# antenna_analyzer_rev7.net
KiCad netlist of a schematic drawn in EAGLE
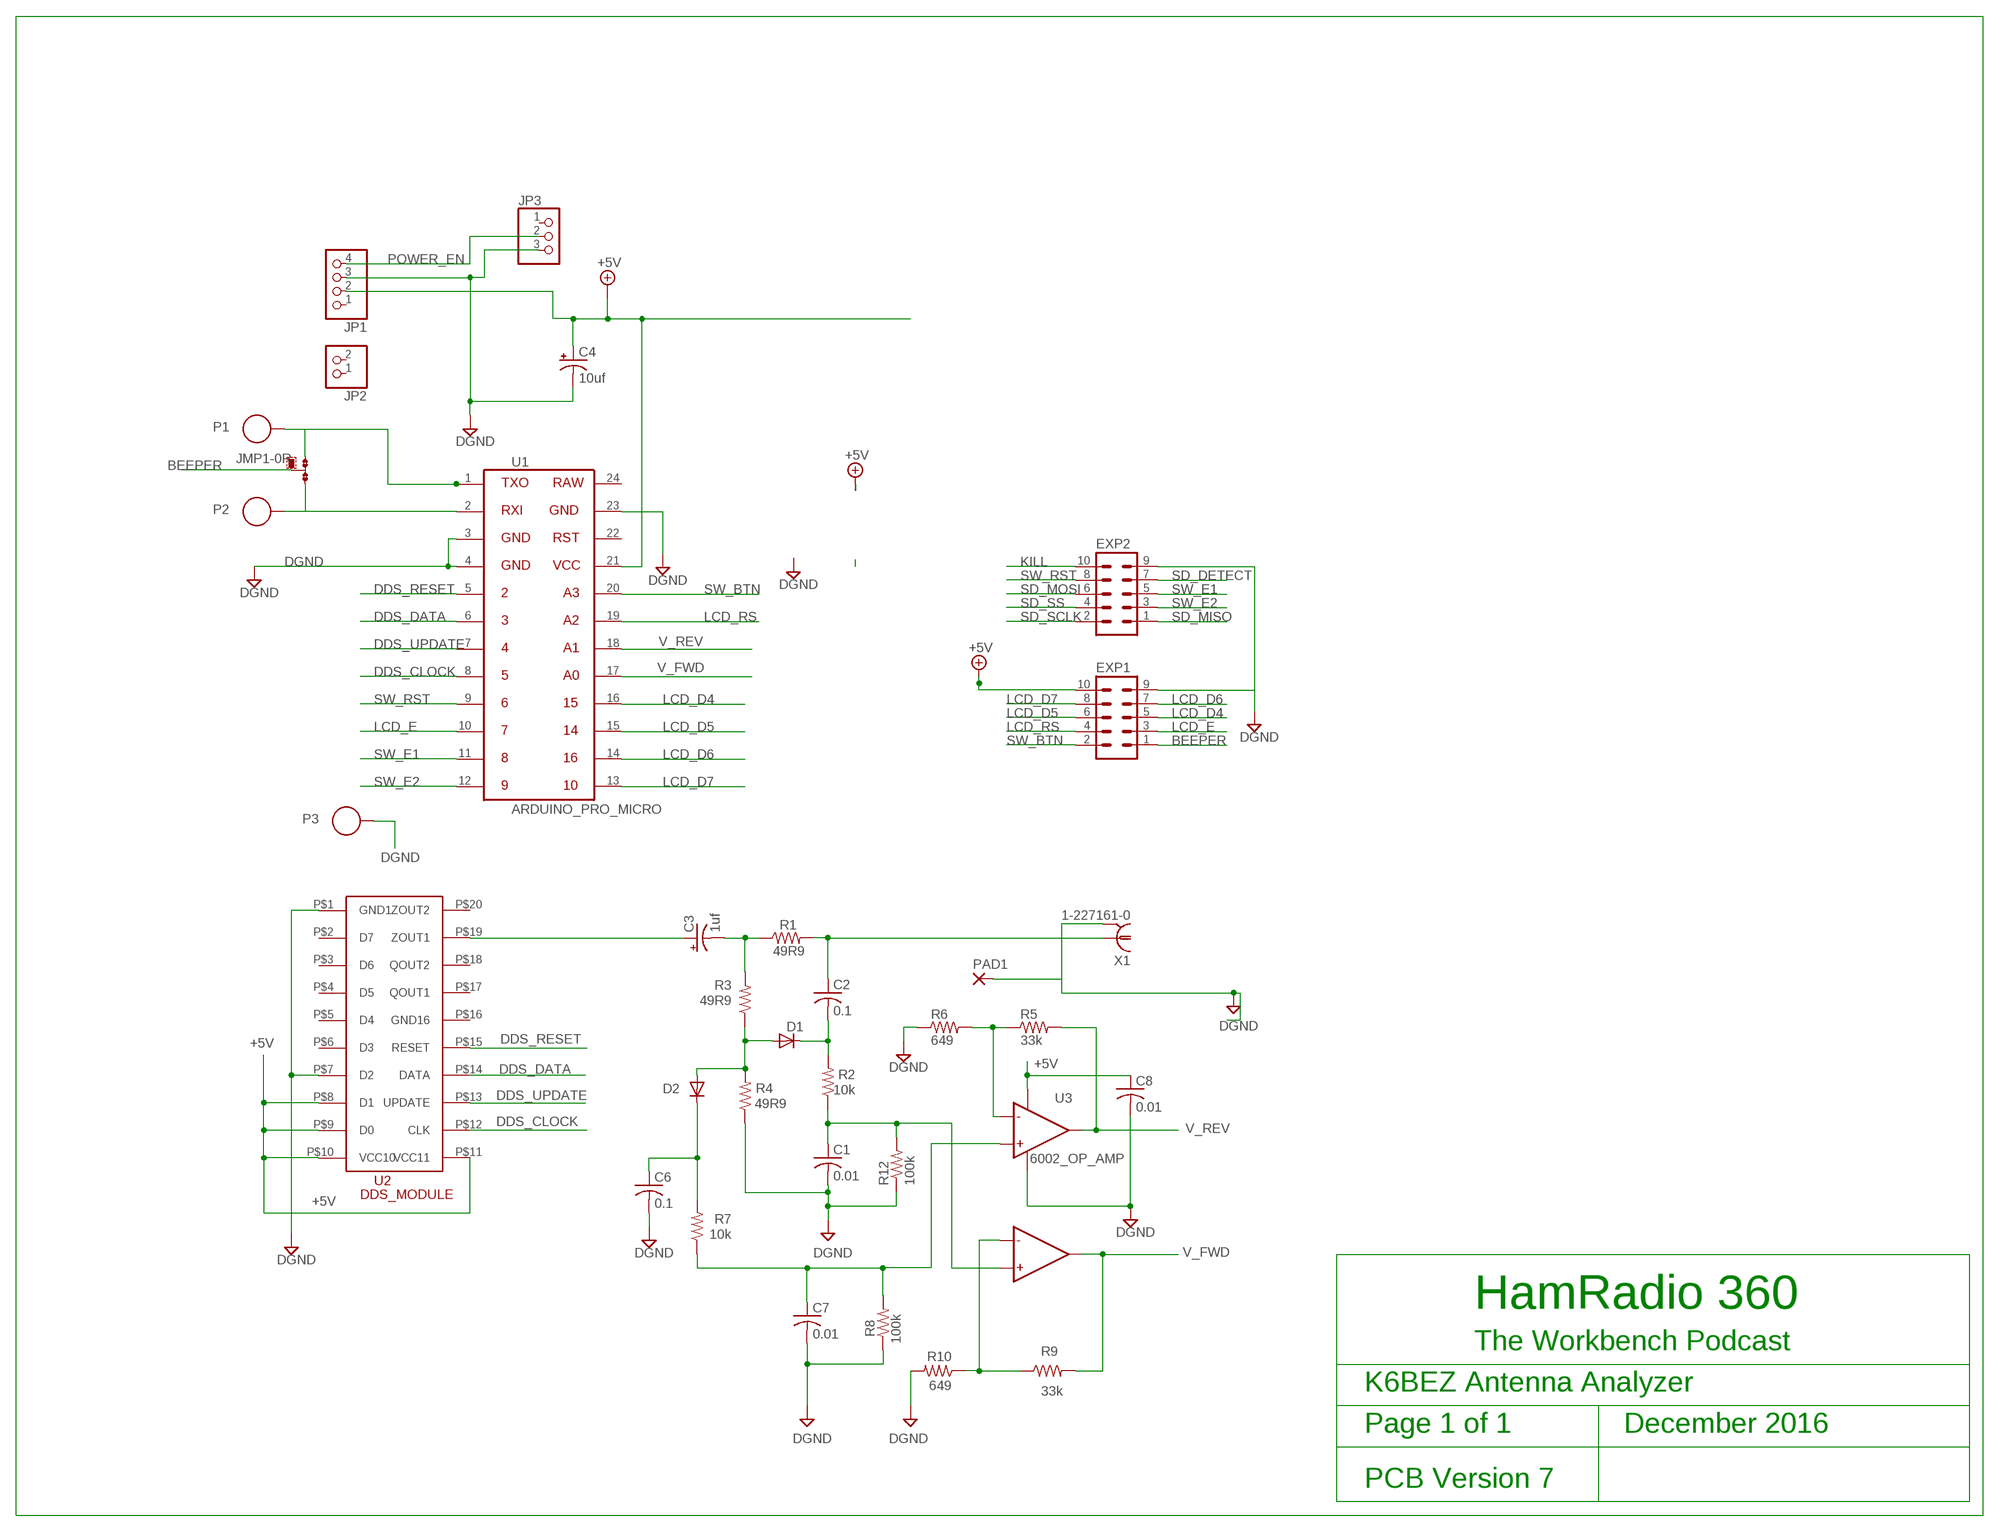
[diagram p0: schematic, sheet 1]

(export (version "E")
  (design (tool "Eeschema 10.0.6"))
  (components
    (comp (ref "C1")
      (value "0.01")
      (footprint "eagle-import:C025-025X050")
      (libsource (lib "eagle-import") (part "C-US025-025X050"))
    )
    (comp (ref "C2")
      (value "0.1")
      (footprint "eagle-import:C025-025X050")
      (libsource (lib "eagle-import") (part "C-US025-025X050"))
    )
    (comp (ref "C3")
      (value "1uf")
      (footprint "eagle-import:E1,8-4")
      (libsource (lib "eagle-import") (part "CPOL-USE1.8-4"))
    )
    (comp (ref "C4")
      (value "10uf")
      (footprint "eagle-import:E1,8-4")
      (libsource (lib "eagle-import") (part "CPOL-USE1.8-4"))
    )
    (comp (ref "C6")
      (value "0.1")
      (footprint "eagle-import:C025-025X050")
      (libsource (lib "eagle-import") (part "C-US025-025X050"))
    )
    (comp (ref "C7")
      (value "0.01")
      (footprint "eagle-import:C025-025X050")
      (libsource (lib "eagle-import") (part "C-US025-025X050"))
    )
    (comp (ref "C8")
      (value "0.01")
      (footprint "eagle-import:C025-025X050")
      (libsource (lib "eagle-import") (part "C-US025-025X050"))
    )
    (comp (ref "D1")
      (value "AA143")
      (footprint "eagle-import:DO35-7")
      (libsource (lib "eagle-import") (part "1N4148DO35-7"))
    )
    (comp (ref "D2")
      (value "AA143")
      (footprint "eagle-import:DO35-7")
      (libsource (lib "eagle-import") (part "1N4148DO35-7"))
    )
    (comp (ref "EXP1")
      (value "MA05-2")
      (footprint "eagle-import:MA05-2")
      (libsource (lib "eagle-import") (part "MA05-2"))
    )
    (comp (ref "EXP2")
      (value "MA05-2")
      (footprint "eagle-import:MA05-2")
      (libsource (lib "eagle-import") (part "MA05-2"))
    )
    (comp (ref "JMP1")
      (value "0R-JUMPA")
      (footprint "eagle-import:A0R-JMP")
      (libsource (lib "eagle-import") (part "0R-JUMPA"))
    )
    (comp (ref "JP1")
      (value "PINHD-1X4")
      (footprint "eagle-import:1X04")
      (libsource (lib "eagle-import") (part "PINHD-1X4"))
    )
    (comp (ref "JP2")
      (value "PINHD-1X2")
      (footprint "eagle-import:1X02")
      (libsource (lib "eagle-import") (part "PINHD-1X2"))
    )
    (comp (ref "JP3")
      (value "PINHD-1X3")
      (footprint "eagle-import:1X03")
      (libsource (lib "eagle-import") (part "PINHD-1X3"))
    )
    (comp (ref "P1")
      (value "SOLDER_PAD_35_HOLE")
      (footprint "eagle-import:SOLDER_PAD_35_HOLE")
      (libsource (lib "eagle-import") (part "SOLDER_PAD_35_HOLE"))
    )
    (comp (ref "P2")
      (value "SOLDER_PAD_35_HOLE")
      (footprint "eagle-import:SOLDER_PAD_35_HOLE")
      (libsource (lib "eagle-import") (part "SOLDER_PAD_35_HOLE"))
    )
    (comp (ref "P3")
      (value "SOLDER_PAD_35_HOLE")
      (footprint "eagle-import:SOLDER_PAD_35_HOLE")
      (libsource (lib "eagle-import") (part "SOLDER_PAD_35_HOLE"))
    )
    (comp (ref "PAD1")
      (value "1,6/0,9")
      (footprint "eagle-import:1,6_0,9")
      (libsource (lib "eagle-import") (part "1,6/0,9"))
    )
    (comp (ref "R1")
      (value "49R9")
      (footprint "eagle-import:0207_10")
      (libsource (lib "eagle-import") (part "R-US_0207/10"))
    )
    (comp (ref "R2")
      (value "10k")
      (footprint "eagle-import:0207_10")
      (libsource (lib "eagle-import") (part "R-US_0207/10"))
    )
    (comp (ref "R3")
      (value "49R9")
      (footprint "eagle-import:0207_10")
      (libsource (lib "eagle-import") (part "R-US_0207/10"))
    )
    (comp (ref "R4")
      (value "49R9")
      (footprint "eagle-import:0207_10")
      (libsource (lib "eagle-import") (part "R-US_0207/10"))
    )
    (comp (ref "R5")
      (value "33k")
      (footprint "eagle-import:0207_10")
      (libsource (lib "eagle-import") (part "R-US_0207/10"))
    )
    (comp (ref "R6")
      (value "649")
      (footprint "eagle-import:0207_10")
      (libsource (lib "eagle-import") (part "R-US_0207/10"))
    )
    (comp (ref "R7")
      (value "10k")
      (footprint "eagle-import:0207_10")
      (libsource (lib "eagle-import") (part "R-US_0207/10"))
    )
    (comp (ref "R8")
      (value "100k")
      (footprint "eagle-import:0207_10")
      (libsource (lib "eagle-import") (part "R-US_0207/10"))
    )
    (comp (ref "R9")
      (value "33k")
      (footprint "eagle-import:0207_10")
      (libsource (lib "eagle-import") (part "R-US_0207/10"))
    )
    (comp (ref "R10")
      (value "649")
      (footprint "eagle-import:0207_10")
      (libsource (lib "eagle-import") (part "R-US_0207/10"))
    )
    (comp (ref "R12")
      (value "100k")
      (footprint "eagle-import:0207_10")
      (libsource (lib "eagle-import") (part "R-US_0207/10"))
    )
    (comp (ref "U1")
      (value "ARDUINO_PRO_MICRO")
      (footprint "eagle-import:ARDUINO_PRO_MICRO")
      (libsource (lib "eagle-import") (part "ARDUINO_PRO_MICRO"))
    )
    (comp (ref "U2")
      (value "AD9850_MOD")
      (footprint "eagle-import:DDS_DIL")
      (libsource (lib "eagle-import") (part "AD9850_MOD"))
    )
    (comp (ref "U3")
      (value "6002_OP_AMP")
      (footprint "eagle-import:OP_AMP_8_PIN")
      (libsource (lib "eagle-import") (part "6002_OP_AMP"))
    )
    (comp (ref "X1")
      (value "1-227161-0")
      (footprint "eagle-import:AMP_227161")
      (fields (field (name "MF") "TYCO ELECTRONICS") (field (name "MPN") "1-227161"))
      (libsource (lib "eagle-import") (part "?2271611--0"))
    )
  )
  (nets
    (net (code "1") (name "+5V") (class "Default")
      (node (ref "C4") (pin "+") (pinfunction "+_+") (pintype "passive"))
      (node (ref "C8") (pin "1") (pinfunction "1_1") (pintype "passive"))
      (node (ref "EXP1") (pin "10") (pinfunction "10_10") (pintype "passive"))
      (node (ref "JP1") (pin "2") (pinfunction "2_2") (pintype "passive"))
      (node (ref "U1") (pin "21") (pinfunction "21_21") (pintype "input"))
      (node (ref "U2") (pin "P$10") (pinfunction "VCC10_P$10") (pintype "bidirectional"))
      (node (ref "U2") (pin "P$11") (pinfunction "VCC11_P$11") (pintype "bidirectional"))
      (node (ref "U2") (pin "P$8") (pinfunction "D1_P$8") (pintype "bidirectional"))
      (node (ref "U2") (pin "P$9") (pinfunction "D0_P$9") (pintype "bidirectional"))
      (node (ref "U3") (pin "8") (pinfunction "VCC+_8") (pintype "power_in"))
    )
    (net (code "2") (name "/BEEPER") (class "Default")
      (node (ref "EXP1") (pin "1") (pinfunction "1_1") (pintype "passive"))
      (node (ref "JMP1") (pin "2") (pinfunction "2_2") (pintype "passive"))
    )
    (net (code "3") (name "/DDS_CLOCK") (class "Default")
      (node (ref "U1") (pin "8") (pinfunction "8_8") (pintype "input"))
      (node (ref "U2") (pin "P$12") (pinfunction "CLK_P$12") (pintype "bidirectional"))
    )
    (net (code "4") (name "/DDS_DATA") (class "Default")
      (node (ref "U1") (pin "6") (pinfunction "6_6") (pintype "input"))
      (node (ref "U2") (pin "P$14") (pinfunction "DATA_P$14") (pintype "bidirectional"))
    )
    (net (code "5") (name "/DDS_RESET") (class "Default")
      (node (ref "U1") (pin "5") (pinfunction "5_5") (pintype "input"))
      (node (ref "U2") (pin "P$15") (pinfunction "RESET_P$15") (pintype "bidirectional"))
    )
    (net (code "6") (name "/DDS_UPDATE") (class "Default")
      (node (ref "U1") (pin "7") (pinfunction "7_7") (pintype "input"))
      (node (ref "U2") (pin "P$13") (pinfunction "UPDATE_P$13") (pintype "bidirectional"))
    )
    (net (code "7") (name "/KILL") (class "Default")
      (node (ref "EXP2") (pin "10") (pinfunction "10_10") (pintype "passive"))
    )
    (net (code "8") (name "/LCD_D4") (class "Default")
      (node (ref "EXP1") (pin "5") (pinfunction "5_5") (pintype "passive"))
      (node (ref "U1") (pin "16") (pinfunction "16_16") (pintype "input"))
    )
    (net (code "9") (name "/LCD_D5") (class "Default")
      (node (ref "EXP1") (pin "6") (pinfunction "6_6") (pintype "passive"))
      (node (ref "U1") (pin "15") (pinfunction "15_15") (pintype "tri_state"))
    )
    (net (code "10") (name "/LCD_D6") (class "Default")
      (node (ref "EXP1") (pin "7") (pinfunction "7_7") (pintype "passive"))
      (node (ref "U1") (pin "14") (pinfunction "14_14") (pintype "input"))
    )
    (net (code "11") (name "/LCD_D7") (class "Default")
      (node (ref "EXP1") (pin "8") (pinfunction "8_8") (pintype "passive"))
      (node (ref "U1") (pin "13") (pinfunction "13_13") (pintype "input"))
    )
    (net (code "12") (name "/LCD_E") (class "Default")
      (node (ref "EXP1") (pin "3") (pinfunction "3_3") (pintype "passive"))
      (node (ref "U1") (pin "10") (pinfunction "10_10") (pintype "input"))
    )
    (net (code "13") (name "/LCD_RS") (class "Default")
      (node (ref "EXP1") (pin "4") (pinfunction "4_4") (pintype "passive"))
      (node (ref "U1") (pin "19") (pinfunction "19_19") (pintype "input"))
    )
    (net (code "15") (name "/POWER_EN") (class "Default")
      (node (ref "JP1") (pin "4") (pinfunction "4_4") (pintype "passive"))
      (node (ref "JP3") (pin "2") (pinfunction "2_2") (pintype "passive"))
    )
    (net (code "16") (name "/SD_DETECT") (class "Default")
      (node (ref "EXP2") (pin "7") (pinfunction "7_7") (pintype "passive"))
    )
    (net (code "17") (name "/SD_MISO") (class "Default")
      (node (ref "EXP2") (pin "1") (pinfunction "1_1") (pintype "passive"))
    )
    (net (code "18") (name "/SD_MOSI") (class "Default")
      (node (ref "EXP2") (pin "6") (pinfunction "6_6") (pintype "passive"))
    )
    (net (code "19") (name "/SD_SCLK") (class "Default")
      (node (ref "EXP2") (pin "2") (pinfunction "2_2") (pintype "passive"))
    )
    (net (code "20") (name "/SD_SS") (class "Default")
      (node (ref "EXP2") (pin "4") (pinfunction "4_4") (pintype "passive"))
    )
    (net (code "21") (name "/SW_BTN") (class "Default")
      (node (ref "EXP1") (pin "2") (pinfunction "2_2") (pintype "passive"))
      (node (ref "U1") (pin "20") (pinfunction "20_20") (pintype "input"))
    )
    (net (code "22") (name "/SW_E1") (class "Default")
      (node (ref "EXP2") (pin "5") (pinfunction "5_5") (pintype "passive"))
      (node (ref "U1") (pin "11") (pinfunction "11_11") (pintype "input"))
    )
    (net (code "23") (name "/SW_E2") (class "Default")
      (node (ref "EXP2") (pin "3") (pinfunction "3_3") (pintype "passive"))
      (node (ref "U1") (pin "12") (pinfunction "12_12") (pintype "input"))
    )
    (net (code "24") (name "/SW_RST") (class "Default")
      (node (ref "EXP2") (pin "8") (pinfunction "8_8") (pintype "passive"))
      (node (ref "U1") (pin "9") (pinfunction "9_9") (pintype "input"))
    )
    (net (code "25") (name "/V_FWD") (class "Default")
      (node (ref "R9") (pin "2") (pinfunction "2_2") (pintype "passive"))
      (node (ref "U1") (pin "17") (pinfunction "17_17") (pintype "input"))
      (node (ref "U3") (pin "7") (pinfunction "OUT2_7") (pintype "output"))
    )
    (net (code "26") (name "/V_REV") (class "Default")
      (node (ref "R5") (pin "2") (pinfunction "2_2") (pintype "passive"))
      (node (ref "U1") (pin "18") (pinfunction "18_18") (pintype "input"))
      (node (ref "U3") (pin "1") (pinfunction "OUT1_1") (pintype "output"))
    )
    (net (code "27") (name "DGND") (class "Default")
      (node (ref "C1") (pin "2") (pinfunction "2_2") (pintype "passive"))
      (node (ref "C4") (pin "-") (pinfunction "-_-") (pintype "passive"))
      (node (ref "C6") (pin "2") (pinfunction "2_2") (pintype "passive"))
      (node (ref "C7") (pin "2") (pinfunction "2_2") (pintype "passive"))
      (node (ref "C8") (pin "2") (pinfunction "2_2") (pintype "passive"))
      (node (ref "EXP1") (pin "9") (pinfunction "9_9") (pintype "passive"))
      (node (ref "EXP2") (pin "9") (pinfunction "9_9") (pintype "passive"))
      (node (ref "JP1") (pin "3") (pinfunction "3_3") (pintype "passive"))
      (node (ref "JP3") (pin "3") (pinfunction "3_3") (pintype "passive"))
      (node (ref "P3") (pin "1") (pinfunction "1_1") (pintype "bidirectional"))
      (node (ref "PAD1") (pin "1") (pinfunction "P_1") (pintype "passive"))
      (node (ref "R10") (pin "2") (pinfunction "2_2") (pintype "passive"))
      (node (ref "R12") (pin "1") (pinfunction "1_1") (pintype "passive"))
      (node (ref "R4") (pin "1") (pinfunction "1_1") (pintype "passive"))
      (node (ref "R6") (pin "1") (pinfunction "1_1") (pintype "passive"))
      (node (ref "R8") (pin "1") (pinfunction "1_1") (pintype "passive"))
      (node (ref "U1") (pin "23") (pinfunction "23_23") (pintype "input"))
      (node (ref "U1") (pin "3") (pinfunction "3_3") (pintype "input"))
      (node (ref "U1") (pin "4") (pinfunction "4_4") (pintype "input"))
      (node (ref "U2") (pin "P$1") (pinfunction "GND1_P$1") (pintype "bidirectional"))
      (node (ref "U2") (pin "P$7") (pinfunction "D2_P$7") (pintype "bidirectional"))
      (node (ref "U3") (pin "4") (pinfunction "VCC-_4") (pintype "power_in"))
      (node (ref "X1") (pin "2") (pinfunction "2_2") (pintype "passive"))
    )
    (net (code "28") (name "Net-(C2-Pad1)") (class "Default")
      (node (ref "C2") (pin "1") (pinfunction "1_1") (pintype "passive"))
      (node (ref "R1") (pin "2") (pinfunction "2_2") (pintype "passive"))
      (node (ref "X1") (pin "1") (pinfunction "1_1") (pintype "passive"))
    )
    (net (code "29") (name "Net-(C2-Pad2)") (class "Default")
      (node (ref "C2") (pin "2") (pinfunction "2_2") (pintype "passive"))
      (node (ref "D1") (pin "C") (pinfunction "C_C") (pintype "passive"))
      (node (ref "R2") (pin "2") (pinfunction "2_2") (pintype "passive"))
    )
    (net (code "30") (name "Net-(C3-Pad-)") (class "Default")
      (node (ref "C3") (pin "-") (pinfunction "-_-") (pintype "passive"))
      (node (ref "R1") (pin "1") (pinfunction "1_1") (pintype "passive"))
      (node (ref "R3") (pin "2") (pinfunction "2_2") (pintype "passive"))
    )
    (net (code "31") (name "Net-(C6-Pad1)") (class "Default")
      (node (ref "C6") (pin "1") (pinfunction "1_1") (pintype "passive"))
      (node (ref "D2") (pin "C") (pinfunction "C_C") (pintype "passive"))
      (node (ref "R7") (pin "2") (pinfunction "2_2") (pintype "passive"))
    )
    (net (code "32") (name "Net-(D1-PadA)") (class "Default")
      (node (ref "D1") (pin "A") (pinfunction "A_A") (pintype "passive"))
      (node (ref "D2") (pin "A") (pinfunction "A_A") (pintype "passive"))
      (node (ref "R3") (pin "1") (pinfunction "1_1") (pintype "passive"))
      (node (ref "R4") (pin "2") (pinfunction "2_2") (pintype "passive"))
    )
    (net (code "33") (name "Net-(JMP1-Pad1)") (class "Default")
      (node (ref "JMP1") (pin "1") (pinfunction "1_1") (pintype "passive"))
      (node (ref "P1") (pin "1") (pinfunction "1_1") (pintype "bidirectional"))
      (node (ref "U1") (pin "1") (pinfunction "1_1") (pintype "input"))
    )
    (net (code "34") (name "Net-(JMP1-Pad3)") (class "Default")
      (node (ref "JMP1") (pin "3") (pinfunction "3_3") (pintype "passive"))
      (node (ref "P2") (pin "1") (pinfunction "1_1") (pintype "bidirectional"))
      (node (ref "U1") (pin "2") (pinfunction "2_2") (pintype "input"))
    )
    (net (code "35") (name "Net-(U2-ZOUT1)") (class "Default")
      (node (ref "C3") (pin "+") (pinfunction "+_+") (pintype "passive"))
      (node (ref "U2") (pin "P$19") (pinfunction "ZOUT1_P$19") (pintype "bidirectional"))
    )
    (net (code "36") (name "Net-(U3-IN+1)") (class "Default")
      (node (ref "C7") (pin "1") (pinfunction "1_1") (pintype "passive"))
      (node (ref "R7") (pin "1") (pinfunction "1_1") (pintype "passive"))
      (node (ref "R8") (pin "2") (pinfunction "2_2") (pintype "passive"))
      (node (ref "U3") (pin "3") (pinfunction "IN+1_3") (pintype "input"))
    )
    (net (code "37") (name "Net-(U3-IN+2)") (class "Default")
      (node (ref "C1") (pin "1") (pinfunction "1_1") (pintype "passive"))
      (node (ref "R12") (pin "2") (pinfunction "2_2") (pintype "passive"))
      (node (ref "R2") (pin "1") (pinfunction "1_1") (pintype "passive"))
      (node (ref "U3") (pin "5") (pinfunction "IN+2_5") (pintype "input"))
    )
    (net (code "38") (name "Net-(U3-IN-1)") (class "Default")
      (node (ref "R5") (pin "1") (pinfunction "1_1") (pintype "passive"))
      (node (ref "R6") (pin "2") (pinfunction "2_2") (pintype "passive"))
      (node (ref "U3") (pin "2") (pinfunction "IN-1_2") (pintype "input"))
    )
    (net (code "39") (name "Net-(U3-IN-2)") (class "Default")
      (node (ref "R10") (pin "1") (pinfunction "1_1") (pintype "passive"))
      (node (ref "R9") (pin "1") (pinfunction "1_1") (pintype "passive"))
      (node (ref "U3") (pin "6") (pinfunction "IN-2_6") (pintype "input"))
    )
    (net (code "40") (name "unconnected-(JP1-Pad1)") (class "Default")
      (node (ref "JP1") (pin "1") (pinfunction "1_1") (pintype "passive"))
    )
    (net (code "41") (name "unconnected-(JP2-Pad1)") (class "Default")
      (node (ref "JP2") (pin "1") (pinfunction "1_1") (pintype "passive"))
    )
    (net (code "42") (name "unconnected-(JP2-Pad2)") (class "Default")
      (node (ref "JP2") (pin "2") (pinfunction "2_2") (pintype "passive"))
    )
    (net (code "43") (name "unconnected-(JP3-Pad1)") (class "Default")
      (node (ref "JP3") (pin "1") (pinfunction "1_1") (pintype "passive"))
    )
    (net (code "44") (name "unconnected-(U1-Pad22)") (class "Default")
      (node (ref "U1") (pin "22") (pinfunction "22_22") (pintype "input"))
    )
    (net (code "45") (name "unconnected-(U1-Pad24)") (class "Default")
      (node (ref "U1") (pin "24") (pinfunction "24_24") (pintype "input"))
    )
    (net (code "46") (name "unconnected-(U2-D3-PadP$6)") (class "Default")
      (node (ref "U2") (pin "P$6") (pinfunction "D3_P$6") (pintype "bidirectional"))
    )
    (net (code "47") (name "unconnected-(U2-D4-PadP$5)") (class "Default")
      (node (ref "U2") (pin "P$5") (pinfunction "D4_P$5") (pintype "bidirectional"))
    )
    (net (code "48") (name "unconnected-(U2-D5-PadP$4)") (class "Default")
      (node (ref "U2") (pin "P$4") (pinfunction "D5_P$4") (pintype "bidirectional"))
    )
    (net (code "49") (name "unconnected-(U2-D6-PadP$3)") (class "Default")
      (node (ref "U2") (pin "P$3") (pinfunction "D6_P$3") (pintype "bidirectional"))
    )
    (net (code "50") (name "unconnected-(U2-D7-PadP$2)") (class "Default")
      (node (ref "U2") (pin "P$2") (pinfunction "D7_P$2") (pintype "bidirectional"))
    )
    (net (code "51") (name "unconnected-(U2-GND16-PadP$16)") (class "Default")
      (node (ref "U2") (pin "P$16") (pinfunction "GND16_P$16") (pintype "bidirectional"))
    )
    (net (code "52") (name "unconnected-(U2-QOUT1-PadP$17)") (class "Default")
      (node (ref "U2") (pin "P$17") (pinfunction "QOUT1_P$17") (pintype "bidirectional"))
    )
    (net (code "53") (name "unconnected-(U2-QOUT2-PadP$18)") (class "Default")
      (node (ref "U2") (pin "P$18") (pinfunction "QOUT2_P$18") (pintype "bidirectional"))
    )
    (net (code "54") (name "unconnected-(U2-ZOUT2-PadP$20)") (class "Default")
      (node (ref "U2") (pin "P$20") (pinfunction "ZOUT2_P$20") (pintype "bidirectional"))
    )
  )
)
